# Sensor.net
KiCad netlist of a schematic drawn in Altium Designer
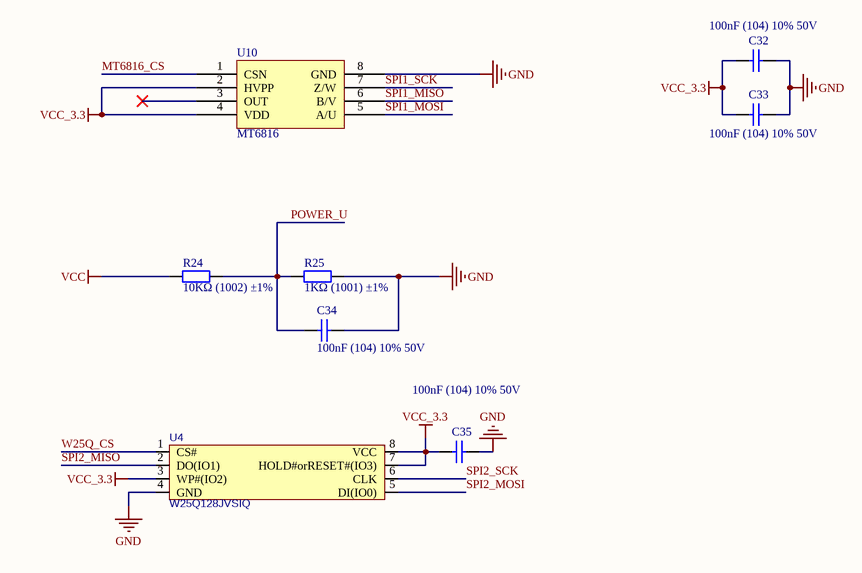
[diagram p0: Sensor.SchDoc]

(export (version "E")
  (design (tool "Eeschema 10.0.6"))
  (components
    (comp (ref "C32")
      (value "100nF (104) 10% 50V")
      (footprint "0603_C")
      (description "贴片电容")
      (libsource (lib "X_Drive") (part "0603 100nF (104) 10% 50V"))
    )
    (comp (ref "C33")
      (value "100nF (104) 10% 50V")
      (footprint "0603_C")
      (description "贴片电容")
      (libsource (lib "X_Drive") (part "0603 100nF (104) 10% 50V"))
    )
    (comp (ref "C34")
      (value "100nF (104) 10% 50V")
      (footprint "0603_C")
      (description "贴片电容")
      (libsource (lib "X_Drive") (part "0603 100nF (104) 10% 50V"))
    )
    (comp (ref "C35")
      (value "100nF (104) 10% 50V")
      (footprint "0603_C")
      (description "贴片电容")
      (libsource (lib "X_Drive") (part "0603 100nF (104) 10% 50V"))
    )
    (comp (ref "R24")
      (value "10KΩ (1002) ±1%")
      (footprint "0603_R")
      (description "贴片电阻")
      (libsource (lib "X_Drive") (part "0603 10KΩ (1002) 1%"))
    )
    (comp (ref "R25")
      (value "1KΩ (1001) ±1%")
      (footprint "0603_R")
      (description "贴片电阻")
      (libsource (lib "X_Drive") (part "0603 1KΩ (1001) 1%"))
    )
    (comp (ref "U4")
      (value "W25Q128JVSIQ")
      (footprint "SOIC-8W")
      (description "SPI FLASH")
      (fields (field (name "1.库作者") "冰凌猫") (field (name "4.作者声明") "旨为整合最全库集,欢迎转载,禁止商用！-冰凌猫"))
      (libsource (lib "1.2 - 存储器-传感元件") (part "W25Q128"))
    )
    (comp (ref "U10")
      (value "MT6816")
      (footprint "SOIC_8")
      (description "磁角度传感器")
      (libsource (lib "X_Drive") (part "MT6816"))
    )
  )
  (nets
    (net (code "1") (name "/MT6816_CS") (class "Default")
      (node (ref "U10") (pin "1") (pinfunction "CSN_1") (pintype "passive"))
    )
    (net (code "2") (name "/POWER_U") (class "Default")
      (node (ref "C34") (pin "1") (pinfunction "1_1") (pintype "passive"))
      (node (ref "R24") (pin "2") (pinfunction "2_2") (pintype "passive"))
      (node (ref "R25") (pin "1") (pinfunction "1_1") (pintype "passive"))
    )
    (net (code "3") (name "/SPI1_MISO") (class "Default")
      (node (ref "U10") (pin "6") (pinfunction "B/V_6") (pintype "passive"))
    )
    (net (code "4") (name "/SPI1_MOSI") (class "Default")
      (node (ref "U10") (pin "5") (pinfunction "A/U_5") (pintype "passive"))
    )
    (net (code "5") (name "/SPI1_SCK") (class "Default")
      (node (ref "U10") (pin "7") (pinfunction "Z/W_7") (pintype "passive"))
    )
    (net (code "6") (name "/SPI2_MISO") (class "Default")
      (node (ref "U4") (pin "2") (pinfunction "DO(IO1)_2") (pintype "passive"))
    )
    (net (code "7") (name "/SPI2_MOSI") (class "Default")
      (node (ref "U4") (pin "5") (pinfunction "DI(IO0)_5") (pintype "passive"))
    )
    (net (code "8") (name "/SPI2_SCK") (class "Default")
      (node (ref "U4") (pin "6") (pinfunction "CLK_6") (pintype "passive"))
    )
    (net (code "9") (name "/W25Q_CS") (class "Default")
      (node (ref "U4") (pin "1") (pinfunction "CS#_1") (pintype "passive"))
    )
    (net (code "10") (name "GND") (class "Default")
      (node (ref "C32") (pin "1") (pinfunction "1_1") (pintype "passive"))
      (node (ref "C33") (pin "1") (pinfunction "1_1") (pintype "passive"))
      (node (ref "C34") (pin "2") (pinfunction "2_2") (pintype "passive"))
      (node (ref "C35") (pin "2") (pinfunction "2_2") (pintype "passive"))
      (node (ref "R25") (pin "2") (pinfunction "2_2") (pintype "passive"))
      (node (ref "U10") (pin "8") (pinfunction "GND_8") (pintype "passive"))
      (node (ref "U4") (pin "4") (pinfunction "GND_4") (pintype "passive"))
    )
    (net (code "11") (name "VCC") (class "Default")
      (node (ref "R24") (pin "1") (pinfunction "1_1") (pintype "passive"))
    )
    (net (code "12") (name "VCC_3.3") (class "Default")
      (node (ref "C32") (pin "2") (pinfunction "2_2") (pintype "passive"))
      (node (ref "C33") (pin "2") (pinfunction "2_2") (pintype "passive"))
      (node (ref "C35") (pin "1") (pinfunction "1_1") (pintype "passive"))
      (node (ref "U10") (pin "2") (pinfunction "HVPP_2") (pintype "passive"))
      (node (ref "U10") (pin "4") (pinfunction "VDD_4") (pintype "passive"))
      (node (ref "U4") (pin "3") (pinfunction "WP#(IO2)_3") (pintype "passive"))
      (node (ref "U4") (pin "7") (pinfunction "HOLD#orRESET#(IO3)_7") (pintype "passive"))
      (node (ref "U4") (pin "8") (pinfunction "VCC_8") (pintype "passive"))
    )
    (net (code "13") (name "unconnected-(U10-OUT-Pad3)") (class "Default")
      (node (ref "U10") (pin "3") (pinfunction "OUT_3") (pintype "passive+no_connect"))
    )
  )
)
